# xenium-progrogrammer-rpi.net
KiCad netlist of a schematic drawn in EAGLE
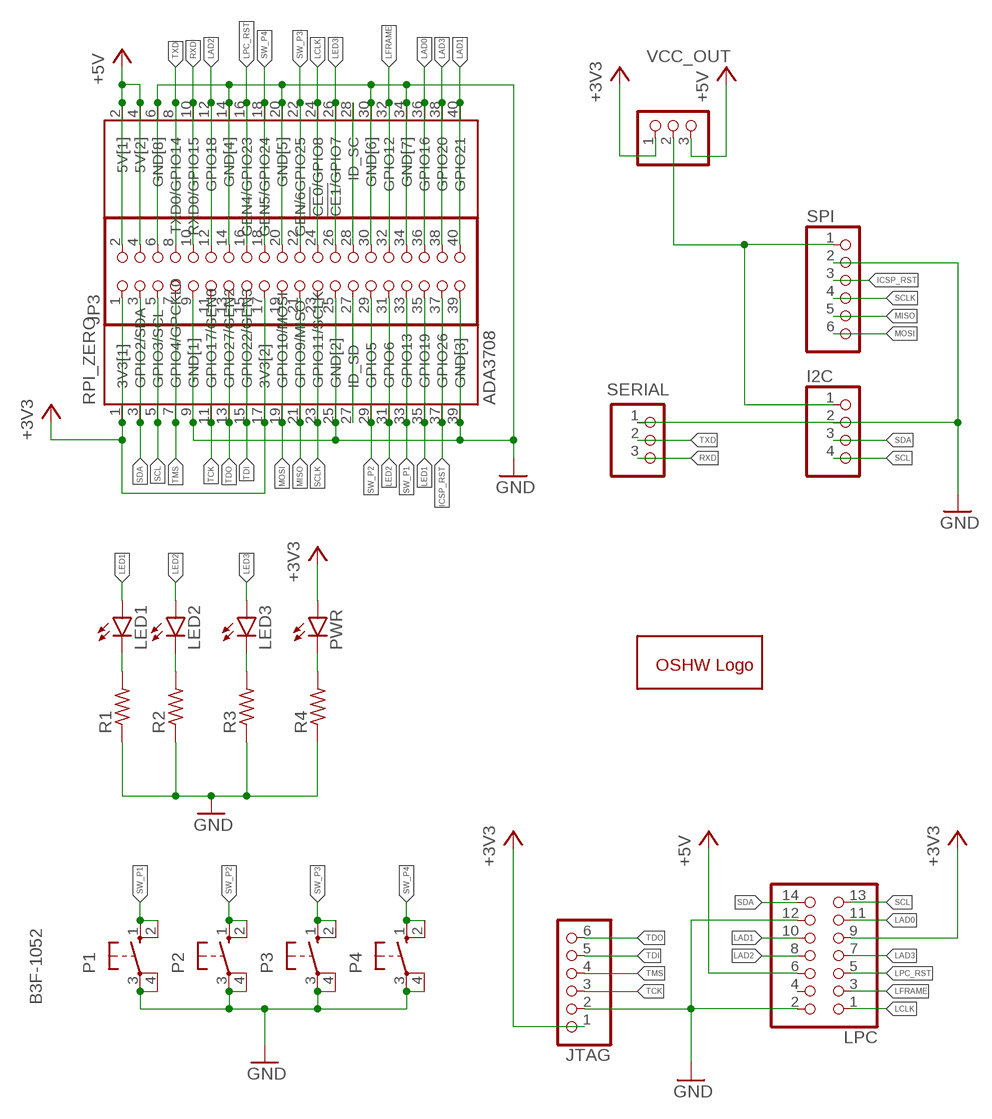
[diagram p0: schematic, sheet 1]

(export (version "E")
  (design (tool "Eeschema 10.0.6"))
  (components
    (comp (ref "GOLD_ORB_SM1")
      (value "OSHWLOGOLOGO8MM")
      (footprint "eagle-import:OSHW_8MM")
      (libsource (lib "eagle-import") (part "OSHWLOGOLOGO8MM"))
    )
    (comp (ref "I2C")
      (value "PINHD-1X4")
      (footprint "eagle-import:1X04")
      (libsource (lib "eagle-import") (part "PINHD-1X4"))
    )
    (comp (ref "JP3")
      (value "PINHD-2X20")
      (footprint "eagle-import:2X20")
      (libsource (lib "eagle-import") (part "PINHD-2X20"))
    )
    (comp (ref "JTAG")
      (value "PINHD-1X6")
      (footprint "eagle-import:1X06")
      (libsource (lib "eagle-import") (part "PINHD-1X6"))
    )
    (comp (ref "LED1")
      (value "LED5MM")
      (footprint "eagle-import:LED5MM")
      (libsource (lib "eagle-import") (part "LED5MM"))
    )
    (comp (ref "LED2")
      (value "LED5MM")
      (footprint "eagle-import:LED5MM")
      (libsource (lib "eagle-import") (part "LED5MM"))
    )
    (comp (ref "LED3")
      (value "LED5MM")
      (footprint "eagle-import:LED5MM")
      (libsource (lib "eagle-import") (part "LED5MM"))
    )
    (comp (ref "LPC")
      (value "PINHD-2X7")
      (footprint "eagle-import:2X07")
      (libsource (lib "eagle-import") (part "PINHD-2X7"))
    )
    (comp (ref "P1")
      (value "B3F-1052")
      (footprint "eagle-import:B3F-10XX")
      (fields (field (name "MF") "Omron"))
      (libsource (lib "eagle-import") (part "B3F-1052"))
    )
    (comp (ref "P2")
      (value "B3F-1052")
      (footprint "eagle-import:B3F-10XX")
      (fields (field (name "MF") "Omron"))
      (libsource (lib "eagle-import") (part "B3F-1052"))
    )
    (comp (ref "P3")
      (value "B3F-1052")
      (footprint "eagle-import:B3F-10XX")
      (fields (field (name "MF") "Omron"))
      (libsource (lib "eagle-import") (part "B3F-1052"))
    )
    (comp (ref "P4")
      (value "B3F-1052")
      (footprint "eagle-import:B3F-10XX")
      (fields (field (name "MF") "Omron"))
      (libsource (lib "eagle-import") (part "B3F-1052"))
    )
    (comp (ref "PWR")
      (value "LED5MM")
      (footprint "eagle-import:LED5MM")
      (libsource (lib "eagle-import") (part "LED5MM"))
    )
    (comp (ref "R1")
      (value "R-US_0207/10")
      (footprint "eagle-import:0207_10")
      (libsource (lib "eagle-import") (part "R-US_0207/10"))
    )
    (comp (ref "R2")
      (value "R-US_0207/10")
      (footprint "eagle-import:0207_10")
      (libsource (lib "eagle-import") (part "R-US_0207/10"))
    )
    (comp (ref "R3")
      (value "R-US_0207/10")
      (footprint "eagle-import:0207_10")
      (libsource (lib "eagle-import") (part "R-US_0207/10"))
    )
    (comp (ref "R4")
      (value "R-US_0207/10")
      (footprint "eagle-import:0207_10")
      (libsource (lib "eagle-import") (part "R-US_0207/10"))
    )
    (comp (ref "RPI_ZERO")
      (value "ADA3708")
      (footprint "eagle-import:ADA3708_RPI-ZERO")
      (fields (field (name "MF") "Raspberry Pi"))
      (libsource (lib "eagle-import") (part "ADA3708"))
    )
    (comp (ref "SERIAL")
      (value "PINHD-1X3")
      (footprint "eagle-import:1X03")
      (libsource (lib "eagle-import") (part "PINHD-1X3"))
    )
    (comp (ref "SPI")
      (value "PINHD-1X6")
      (footprint "eagle-import:1X06")
      (libsource (lib "eagle-import") (part "PINHD-1X6"))
    )
    (comp (ref "VCC_OUT")
      (value "PINHD-1X3")
      (footprint "eagle-import:1X03")
      (libsource (lib "eagle-import") (part "PINHD-1X3"))
    )
  )
  (nets
    (net (code "1") (name "+3V3") (class "Default")
      (node (ref "JP3") (pin "1") (pinfunction "1_1") (pintype "passive"))
      (node (ref "JP3") (pin "17") (pinfunction "17_17") (pintype "passive"))
      (node (ref "JTAG") (pin "1") (pinfunction "1_1") (pintype "passive"))
      (node (ref "LPC") (pin "9") (pinfunction "9_9") (pintype "passive"))
      (node (ref "PWR") (pin "A") (pinfunction "A_A") (pintype "passive"))
      (node (ref "RPI_ZERO") (pin "1") (pinfunction "3V3[1]_1") (pintype "power_in"))
      (node (ref "RPI_ZERO") (pin "17") (pinfunction "3V3[2]_17") (pintype "power_in"))
      (node (ref "VCC_OUT") (pin "1") (pinfunction "1_1") (pintype "passive"))
    )
    (net (code "2") (name "+5V") (class "Default")
      (node (ref "JP3") (pin "2") (pinfunction "2_2") (pintype "passive"))
      (node (ref "JP3") (pin "4") (pinfunction "4_4") (pintype "passive"))
      (node (ref "LPC") (pin "6") (pinfunction "6_6") (pintype "passive"))
      (node (ref "RPI_ZERO") (pin "2") (pinfunction "5V[1]_2") (pintype "power_in"))
      (node (ref "RPI_ZERO") (pin "4") (pinfunction "5V[2]_4") (pintype "power_in"))
      (node (ref "VCC_OUT") (pin "3") (pinfunction "3_3") (pintype "passive"))
    )
    (net (code "3") (name "GND") (class "Default")
      (node (ref "I2C") (pin "2") (pinfunction "2_2") (pintype "passive"))
      (node (ref "JP3") (pin "14") (pinfunction "14_14") (pintype "passive"))
      (node (ref "JP3") (pin "20") (pinfunction "20_20") (pintype "passive"))
      (node (ref "JP3") (pin "25") (pinfunction "25_25") (pintype "passive"))
      (node (ref "JP3") (pin "30") (pinfunction "30_30") (pintype "passive"))
      (node (ref "JP3") (pin "34") (pinfunction "34_34") (pintype "passive"))
      (node (ref "JP3") (pin "39") (pinfunction "39_39") (pintype "passive"))
      (node (ref "JP3") (pin "6") (pinfunction "6_6") (pintype "passive"))
      (node (ref "JP3") (pin "9") (pinfunction "9_9") (pintype "passive"))
      (node (ref "JTAG") (pin "2") (pinfunction "2_2") (pintype "passive"))
      (node (ref "LPC") (pin "12") (pinfunction "12_12") (pintype "passive"))
      (node (ref "LPC") (pin "2") (pinfunction "2_2") (pintype "passive"))
      (node (ref "P1") (pin "3") (pinfunction "P_3") (pintype "passive"))
      (node (ref "P1") (pin "4") (pinfunction "P1_4") (pintype "passive"))
      (node (ref "P2") (pin "3") (pinfunction "P_3") (pintype "passive"))
      (node (ref "P2") (pin "4") (pinfunction "P1_4") (pintype "passive"))
      (node (ref "P3") (pin "3") (pinfunction "P_3") (pintype "passive"))
      (node (ref "P3") (pin "4") (pinfunction "P1_4") (pintype "passive"))
      (node (ref "P4") (pin "3") (pinfunction "P_3") (pintype "passive"))
      (node (ref "P4") (pin "4") (pinfunction "P1_4") (pintype "passive"))
      (node (ref "R1") (pin "1") (pinfunction "1_1") (pintype "passive"))
      (node (ref "R2") (pin "1") (pinfunction "1_1") (pintype "passive"))
      (node (ref "R3") (pin "1") (pinfunction "1_1") (pintype "passive"))
      (node (ref "R4") (pin "1") (pinfunction "1_1") (pintype "passive"))
      (node (ref "RPI_ZERO") (pin "14") (pinfunction "GND[4]_14") (pintype "power_in"))
      (node (ref "RPI_ZERO") (pin "20") (pinfunction "GND[5]_20") (pintype "power_in"))
      (node (ref "RPI_ZERO") (pin "25") (pinfunction "GND[2]_25") (pintype "power_in"))
      (node (ref "RPI_ZERO") (pin "30") (pinfunction "GND[6]_30") (pintype "power_in"))
      (node (ref "RPI_ZERO") (pin "34") (pinfunction "GND[7]_34") (pintype "power_in"))
      (node (ref "RPI_ZERO") (pin "39") (pinfunction "GND[3]_39") (pintype "power_in"))
      (node (ref "RPI_ZERO") (pin "6") (pinfunction "GND[8]_6") (pintype "power_in"))
      (node (ref "RPI_ZERO") (pin "9") (pinfunction "GND[1]_9") (pintype "power_in"))
      (node (ref "SERIAL") (pin "1") (pinfunction "1_1") (pintype "passive"))
      (node (ref "SPI") (pin "2") (pinfunction "2_2") (pintype "passive"))
    )
    (net (code "4") (name "ICSP_RST") (class "Default")
      (node (ref "JP3") (pin "37") (pinfunction "37_37") (pintype "passive"))
      (node (ref "RPI_ZERO") (pin "37") (pinfunction "GPIO26_37") (pintype "bidirectional"))
      (node (ref "SPI") (pin "3") (pinfunction "3_3") (pintype "passive"))
    )
    (net (code "5") (name "LAD0") (class "Default")
      (node (ref "JP3") (pin "36") (pinfunction "36_36") (pintype "passive"))
      (node (ref "LPC") (pin "11") (pinfunction "11_11") (pintype "passive"))
      (node (ref "RPI_ZERO") (pin "36") (pinfunction "GPIO16_36") (pintype "bidirectional"))
    )
    (net (code "6") (name "LAD1") (class "Default")
      (node (ref "JP3") (pin "40") (pinfunction "40_40") (pintype "passive"))
      (node (ref "LPC") (pin "10") (pinfunction "10_10") (pintype "passive"))
      (node (ref "RPI_ZERO") (pin "40") (pinfunction "GPIO21_40") (pintype "bidirectional"))
    )
    (net (code "7") (name "LAD2") (class "Default")
      (node (ref "JP3") (pin "12") (pinfunction "12_12") (pintype "passive"))
      (node (ref "LPC") (pin "8") (pinfunction "8_8") (pintype "passive"))
      (node (ref "RPI_ZERO") (pin "12") (pinfunction "GPIO18_12") (pintype "bidirectional"))
    )
    (net (code "8") (name "LAD3") (class "Default")
      (node (ref "JP3") (pin "38") (pinfunction "38_38") (pintype "passive"))
      (node (ref "LPC") (pin "7") (pinfunction "7_7") (pintype "passive"))
      (node (ref "RPI_ZERO") (pin "38") (pinfunction "GPIO20_38") (pintype "bidirectional"))
    )
    (net (code "9") (name "LCLK") (class "Default")
      (node (ref "JP3") (pin "24") (pinfunction "24_24") (pintype "passive"))
      (node (ref "LPC") (pin "1") (pinfunction "1_1") (pintype "passive"))
      (node (ref "RPI_ZERO") (pin "24") (pinfunction "~{CE0}/GPIO8_24") (pintype "bidirectional"))
    )
    (net (code "10") (name "LED1") (class "Default")
      (node (ref "JP3") (pin "35") (pinfunction "35_35") (pintype "passive"))
      (node (ref "LED1") (pin "A") (pinfunction "A_A") (pintype "passive"))
      (node (ref "RPI_ZERO") (pin "35") (pinfunction "GPIO19_35") (pintype "bidirectional"))
    )
    (net (code "11") (name "LED2") (class "Default")
      (node (ref "JP3") (pin "31") (pinfunction "31_31") (pintype "passive"))
      (node (ref "LED2") (pin "A") (pinfunction "A_A") (pintype "passive"))
      (node (ref "RPI_ZERO") (pin "31") (pinfunction "GPIO6_31") (pintype "bidirectional"))
    )
    (net (code "12") (name "LED3") (class "Default")
      (node (ref "JP3") (pin "26") (pinfunction "26_26") (pintype "passive"))
      (node (ref "LED3") (pin "A") (pinfunction "A_A") (pintype "passive"))
      (node (ref "RPI_ZERO") (pin "26") (pinfunction "~{CE1/}GPIO7_26") (pintype "bidirectional"))
    )
    (net (code "13") (name "LFRAME") (class "Default")
      (node (ref "JP3") (pin "32") (pinfunction "32_32") (pintype "passive"))
      (node (ref "LPC") (pin "3") (pinfunction "3_3") (pintype "passive"))
      (node (ref "RPI_ZERO") (pin "32") (pinfunction "GPIO12_32") (pintype "bidirectional"))
    )
    (net (code "14") (name "LPC_RST") (class "Default")
      (node (ref "JP3") (pin "16") (pinfunction "16_16") (pintype "passive"))
      (node (ref "LPC") (pin "5") (pinfunction "5_5") (pintype "passive"))
      (node (ref "RPI_ZERO") (pin "16") (pinfunction "GEN4/GPIO23_16") (pintype "bidirectional"))
    )
    (net (code "15") (name "MISO") (class "Default")
      (node (ref "JP3") (pin "21") (pinfunction "21_21") (pintype "passive"))
      (node (ref "RPI_ZERO") (pin "21") (pinfunction "GPIO9/MISO_21") (pintype "bidirectional"))
      (node (ref "SPI") (pin "5") (pinfunction "5_5") (pintype "passive"))
    )
    (net (code "16") (name "MOSI") (class "Default")
      (node (ref "JP3") (pin "19") (pinfunction "19_19") (pintype "passive"))
      (node (ref "RPI_ZERO") (pin "19") (pinfunction "GPIO10/MOSI_19") (pintype "bidirectional"))
      (node (ref "SPI") (pin "6") (pinfunction "6_6") (pintype "passive"))
    )
    (net (code "17") (name "Net-(I2C-Pad1)") (class "Default")
      (node (ref "I2C") (pin "1") (pinfunction "1_1") (pintype "passive"))
      (node (ref "SPI") (pin "1") (pinfunction "1_1") (pintype "passive"))
      (node (ref "VCC_OUT") (pin "2") (pinfunction "2_2") (pintype "passive"))
    )
    (net (code "18") (name "Net-(LED1-C)") (class "Default")
      (node (ref "LED1") (pin "K") (pinfunction "C_K") (pintype "passive"))
      (node (ref "R1") (pin "2") (pinfunction "2_2") (pintype "passive"))
    )
    (net (code "19") (name "Net-(LED2-C)") (class "Default")
      (node (ref "LED2") (pin "K") (pinfunction "C_K") (pintype "passive"))
      (node (ref "R2") (pin "2") (pinfunction "2_2") (pintype "passive"))
    )
    (net (code "20") (name "Net-(LED3-C)") (class "Default")
      (node (ref "LED3") (pin "K") (pinfunction "C_K") (pintype "passive"))
      (node (ref "R3") (pin "2") (pinfunction "2_2") (pintype "passive"))
    )
    (net (code "21") (name "Net-(PWR-C)") (class "Default")
      (node (ref "PWR") (pin "K") (pinfunction "C_K") (pintype "passive"))
      (node (ref "R4") (pin "2") (pinfunction "2_2") (pintype "passive"))
    )
    (net (code "22") (name "Net-(RPI_ZERO-ID_SC)") (class "Default")
      (node (ref "JP3") (pin "28") (pinfunction "28_28") (pintype "passive"))
      (node (ref "RPI_ZERO") (pin "28") (pinfunction "ID_SC_28") (pintype "bidirectional"))
    )
    (net (code "23") (name "Net-(RPI_ZERO-ID_SD)") (class "Default")
      (node (ref "JP3") (pin "27") (pinfunction "27_27") (pintype "passive"))
      (node (ref "RPI_ZERO") (pin "27") (pinfunction "ID_SD_27") (pintype "bidirectional"))
    )
    (net (code "24") (name "RXD") (class "Default")
      (node (ref "JP3") (pin "10") (pinfunction "10_10") (pintype "passive"))
      (node (ref "RPI_ZERO") (pin "10") (pinfunction "RXD0/GPIO15_10") (pintype "bidirectional"))
      (node (ref "SERIAL") (pin "3") (pinfunction "3_3") (pintype "passive"))
    )
    (net (code "25") (name "SCL") (class "Default")
      (node (ref "I2C") (pin "4") (pinfunction "4_4") (pintype "passive"))
      (node (ref "JP3") (pin "5") (pinfunction "5_5") (pintype "passive"))
      (node (ref "LPC") (pin "13") (pinfunction "13_13") (pintype "passive"))
      (node (ref "RPI_ZERO") (pin "5") (pinfunction "GPIO3/SCL_5") (pintype "bidirectional"))
    )
    (net (code "26") (name "SCLK") (class "Default")
      (node (ref "JP3") (pin "23") (pinfunction "23_23") (pintype "passive"))
      (node (ref "RPI_ZERO") (pin "23") (pinfunction "GPIO11/SCLK_23") (pintype "bidirectional"))
      (node (ref "SPI") (pin "4") (pinfunction "4_4") (pintype "passive"))
    )
    (net (code "27") (name "SDA") (class "Default")
      (node (ref "I2C") (pin "3") (pinfunction "3_3") (pintype "passive"))
      (node (ref "JP3") (pin "3") (pinfunction "3_3") (pintype "passive"))
      (node (ref "LPC") (pin "14") (pinfunction "14_14") (pintype "passive"))
      (node (ref "RPI_ZERO") (pin "3") (pinfunction "GPIO2/SDA_3") (pintype "bidirectional"))
    )
    (net (code "28") (name "SW_P1") (class "Default")
      (node (ref "JP3") (pin "33") (pinfunction "33_33") (pintype "passive"))
      (node (ref "P1") (pin "1") (pinfunction "S_1") (pintype "passive"))
      (node (ref "P1") (pin "2") (pinfunction "S1_2") (pintype "passive"))
      (node (ref "RPI_ZERO") (pin "33") (pinfunction "GPIO13_33") (pintype "bidirectional"))
    )
    (net (code "29") (name "SW_P2") (class "Default")
      (node (ref "JP3") (pin "29") (pinfunction "29_29") (pintype "passive"))
      (node (ref "P2") (pin "1") (pinfunction "S_1") (pintype "passive"))
      (node (ref "P2") (pin "2") (pinfunction "S1_2") (pintype "passive"))
      (node (ref "RPI_ZERO") (pin "29") (pinfunction "GPIO5_29") (pintype "bidirectional"))
    )
    (net (code "30") (name "SW_P3") (class "Default")
      (node (ref "JP3") (pin "22") (pinfunction "22_22") (pintype "passive"))
      (node (ref "P3") (pin "1") (pinfunction "S_1") (pintype "passive"))
      (node (ref "P3") (pin "2") (pinfunction "S1_2") (pintype "passive"))
      (node (ref "RPI_ZERO") (pin "22") (pinfunction "GEN/6GPIO25_22") (pintype "bidirectional"))
    )
    (net (code "31") (name "SW_P4") (class "Default")
      (node (ref "JP3") (pin "18") (pinfunction "18_18") (pintype "passive"))
      (node (ref "P4") (pin "1") (pinfunction "S_1") (pintype "passive"))
      (node (ref "P4") (pin "2") (pinfunction "S1_2") (pintype "passive"))
      (node (ref "RPI_ZERO") (pin "18") (pinfunction "GEN5/GPIO24_18") (pintype "bidirectional"))
    )
    (net (code "32") (name "TCK") (class "Default")
      (node (ref "JP3") (pin "11") (pinfunction "11_11") (pintype "passive"))
      (node (ref "JTAG") (pin "3") (pinfunction "3_3") (pintype "passive"))
      (node (ref "RPI_ZERO") (pin "11") (pinfunction "GPIO17/GEN0_11") (pintype "bidirectional"))
    )
    (net (code "33") (name "TDI") (class "Default")
      (node (ref "JP3") (pin "15") (pinfunction "15_15") (pintype "passive"))
      (node (ref "JTAG") (pin "5") (pinfunction "5_5") (pintype "passive"))
      (node (ref "RPI_ZERO") (pin "15") (pinfunction "GPIO22/GEN3_15") (pintype "bidirectional"))
    )
    (net (code "34") (name "TDO") (class "Default")
      (node (ref "JP3") (pin "13") (pinfunction "13_13") (pintype "passive"))
      (node (ref "JTAG") (pin "6") (pinfunction "6_6") (pintype "passive"))
      (node (ref "RPI_ZERO") (pin "13") (pinfunction "GPIO27/GEN2_13") (pintype "bidirectional"))
    )
    (net (code "35") (name "TMS") (class "Default")
      (node (ref "JP3") (pin "7") (pinfunction "7_7") (pintype "passive"))
      (node (ref "JTAG") (pin "4") (pinfunction "4_4") (pintype "passive"))
      (node (ref "RPI_ZERO") (pin "7") (pinfunction "GPIO4/GPCKL0_7") (pintype "bidirectional"))
    )
    (net (code "36") (name "TXD") (class "Default")
      (node (ref "JP3") (pin "8") (pinfunction "8_8") (pintype "passive"))
      (node (ref "RPI_ZERO") (pin "8") (pinfunction "TXD0/GPIO14_8") (pintype "bidirectional"))
      (node (ref "SERIAL") (pin "2") (pinfunction "2_2") (pintype "passive"))
    )
    (net (code "37") (name "unconnected-(LPC-Pad4)") (class "Default")
      (node (ref "LPC") (pin "4") (pinfunction "4_4") (pintype "passive"))
    )
  )
)
